# badge.net
KiCad netlist of a schematic drawn in EAGLE
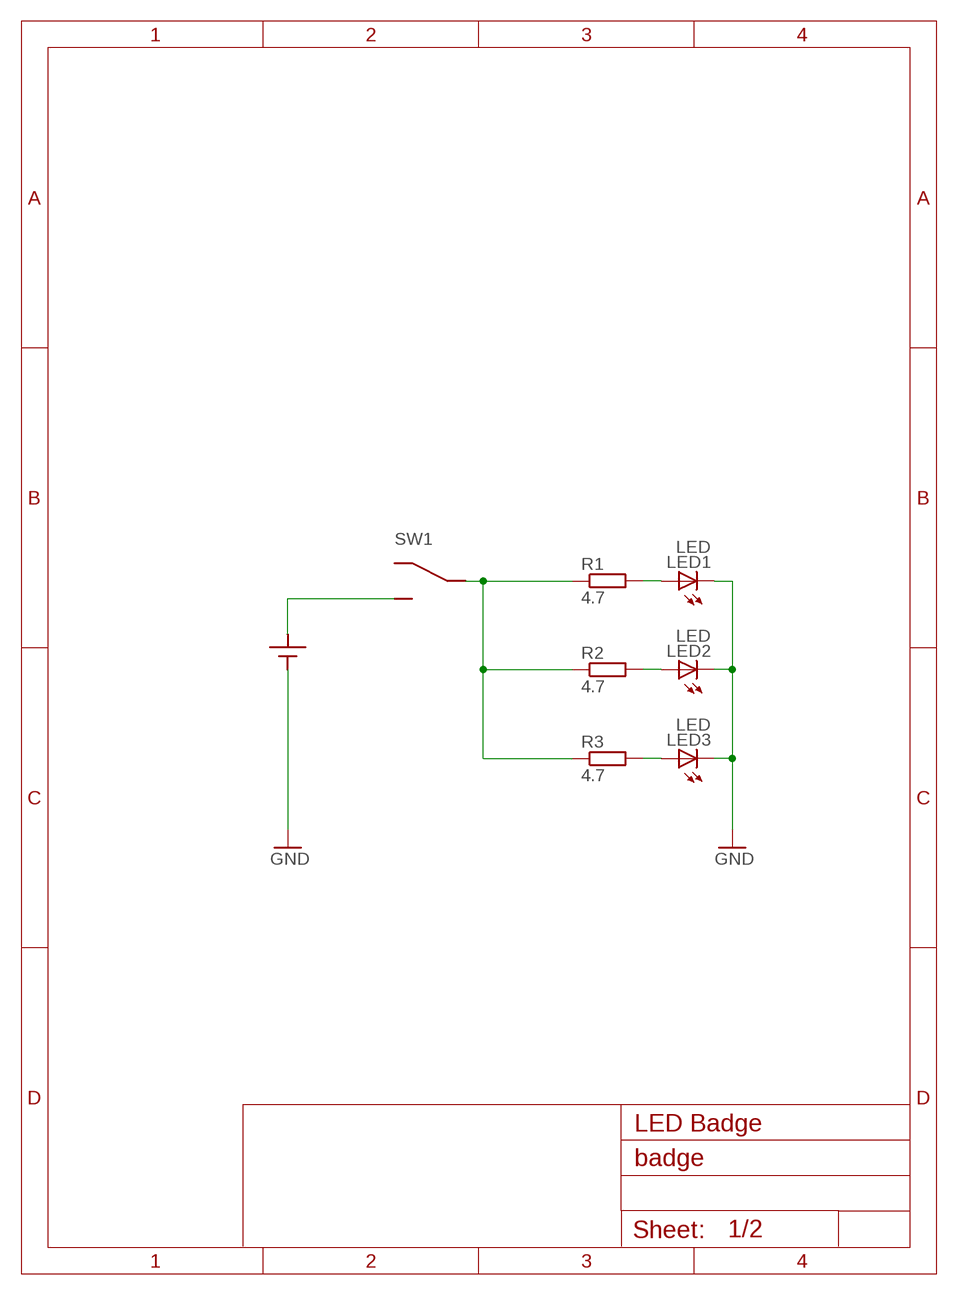
[diagram p0: schematic, sheet 1]
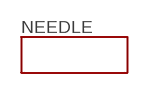
[diagram p1: schematic, sheet 2]

(export (version "E")
  (design (tool "Eeschema 10.0.6"))
  (components
    (comp (ref "NEEDLE")
      (value "NEEDLE")
      (footprint "eagle-import:NEEDLE_PAD")
      (libsource (lib "eagle-import") (part "NEEDLE"))
    )
    (comp (ref "LED1")
      (value "LED")
      (footprint "eagle-import:LED5MM")
      (libsource (lib "eagle-import") (part "LED"))
    )
    (comp (ref "LED2")
      (value "LED")
      (footprint "eagle-import:LED5MM")
      (libsource (lib "eagle-import") (part "LED"))
    )
    (comp (ref "LED3")
      (value "LED")
      (footprint "eagle-import:LED5MM")
      (libsource (lib "eagle-import") (part "LED"))
    )
    (comp (ref "R1")
      (value "4.7")
      (footprint "eagle-import:0207_10")
      (libsource (lib "eagle-import") (part "RESISTOR_207"))
    )
    (comp (ref "R2")
      (value "4.7")
      (footprint "eagle-import:0207_10")
      (libsource (lib "eagle-import") (part "RESISTOR_207"))
    )
    (comp (ref "R3")
      (value "4.7")
      (footprint "eagle-import:0207_10")
      (libsource (lib "eagle-import") (part "RESISTOR_207"))
    )
    (comp (ref "SW1")
      (value "SWITCH")
      (footprint "eagle-import:SWITCH")
      (libsource (lib "eagle-import") (part "SWITCH"))
    )
    (comp (ref "X1")
      (value "BATTERYHOLDER_SMD")
      (footprint "eagle-import:BATTERYHOLDER_SMD")
      (libsource (lib "eagle-import") (part "BATTERYHOLDER_SMD"))
    )
  )
  (nets
    (net (code "1") (name "GND") (class "Default")
      (node (ref "LED1") (pin "K") (pinfunction "C_K") (pintype "passive"))
      (node (ref "LED2") (pin "K") (pinfunction "C_K") (pintype "passive"))
      (node (ref "LED3") (pin "K") (pinfunction "C_K") (pintype "passive"))
      (node (ref "X1") (pin "-") (pinfunction "-_-") (pintype "power_in"))
    )
    (net (code "2") (name "Net-(LED1-PadA)") (class "Default")
      (node (ref "LED1") (pin "A") (pinfunction "A_A") (pintype "passive"))
      (node (ref "R1") (pin "2") (pinfunction "2_2") (pintype "passive"))
    )
    (net (code "3") (name "Net-(LED2-PadA)") (class "Default")
      (node (ref "LED2") (pin "A") (pinfunction "A_A") (pintype "passive"))
      (node (ref "R2") (pin "2") (pinfunction "2_2") (pintype "passive"))
    )
    (net (code "4") (name "Net-(LED3-PadA)") (class "Default")
      (node (ref "LED3") (pin "A") (pinfunction "A_A") (pintype "passive"))
      (node (ref "R3") (pin "2") (pinfunction "2_2") (pintype "passive"))
    )
    (net (code "5") (name "Net-(R1-Pad1)") (class "Default")
      (node (ref "R1") (pin "1") (pinfunction "1_1") (pintype "passive"))
      (node (ref "R2") (pin "1") (pinfunction "1_1") (pintype "passive"))
      (node (ref "R3") (pin "1") (pinfunction "1_1") (pintype "passive"))
      (node (ref "SW1") (pin "C") (pinfunction "C_C") (pintype "bidirectional"))
    )
    (net (code "6") (name "Net-(SW1-PadNO)") (class "Default")
      (node (ref "SW1") (pin "NO") (pinfunction "NO_NO") (pintype "bidirectional"))
      (node (ref "X1") (pin "+") (pinfunction "+_+") (pintype "power_in"))
    )
    (net (code "7") (name "unconnected-(SW1-PadNC)") (class "Default")
      (node (ref "SW1") (pin "NC") (pinfunction "NC_NC") (pintype "bidirectional"))
    )
  )
)
